# LAN8830_PINOUT.net
KiCad netlist of a schematic drawn in Altium Designer
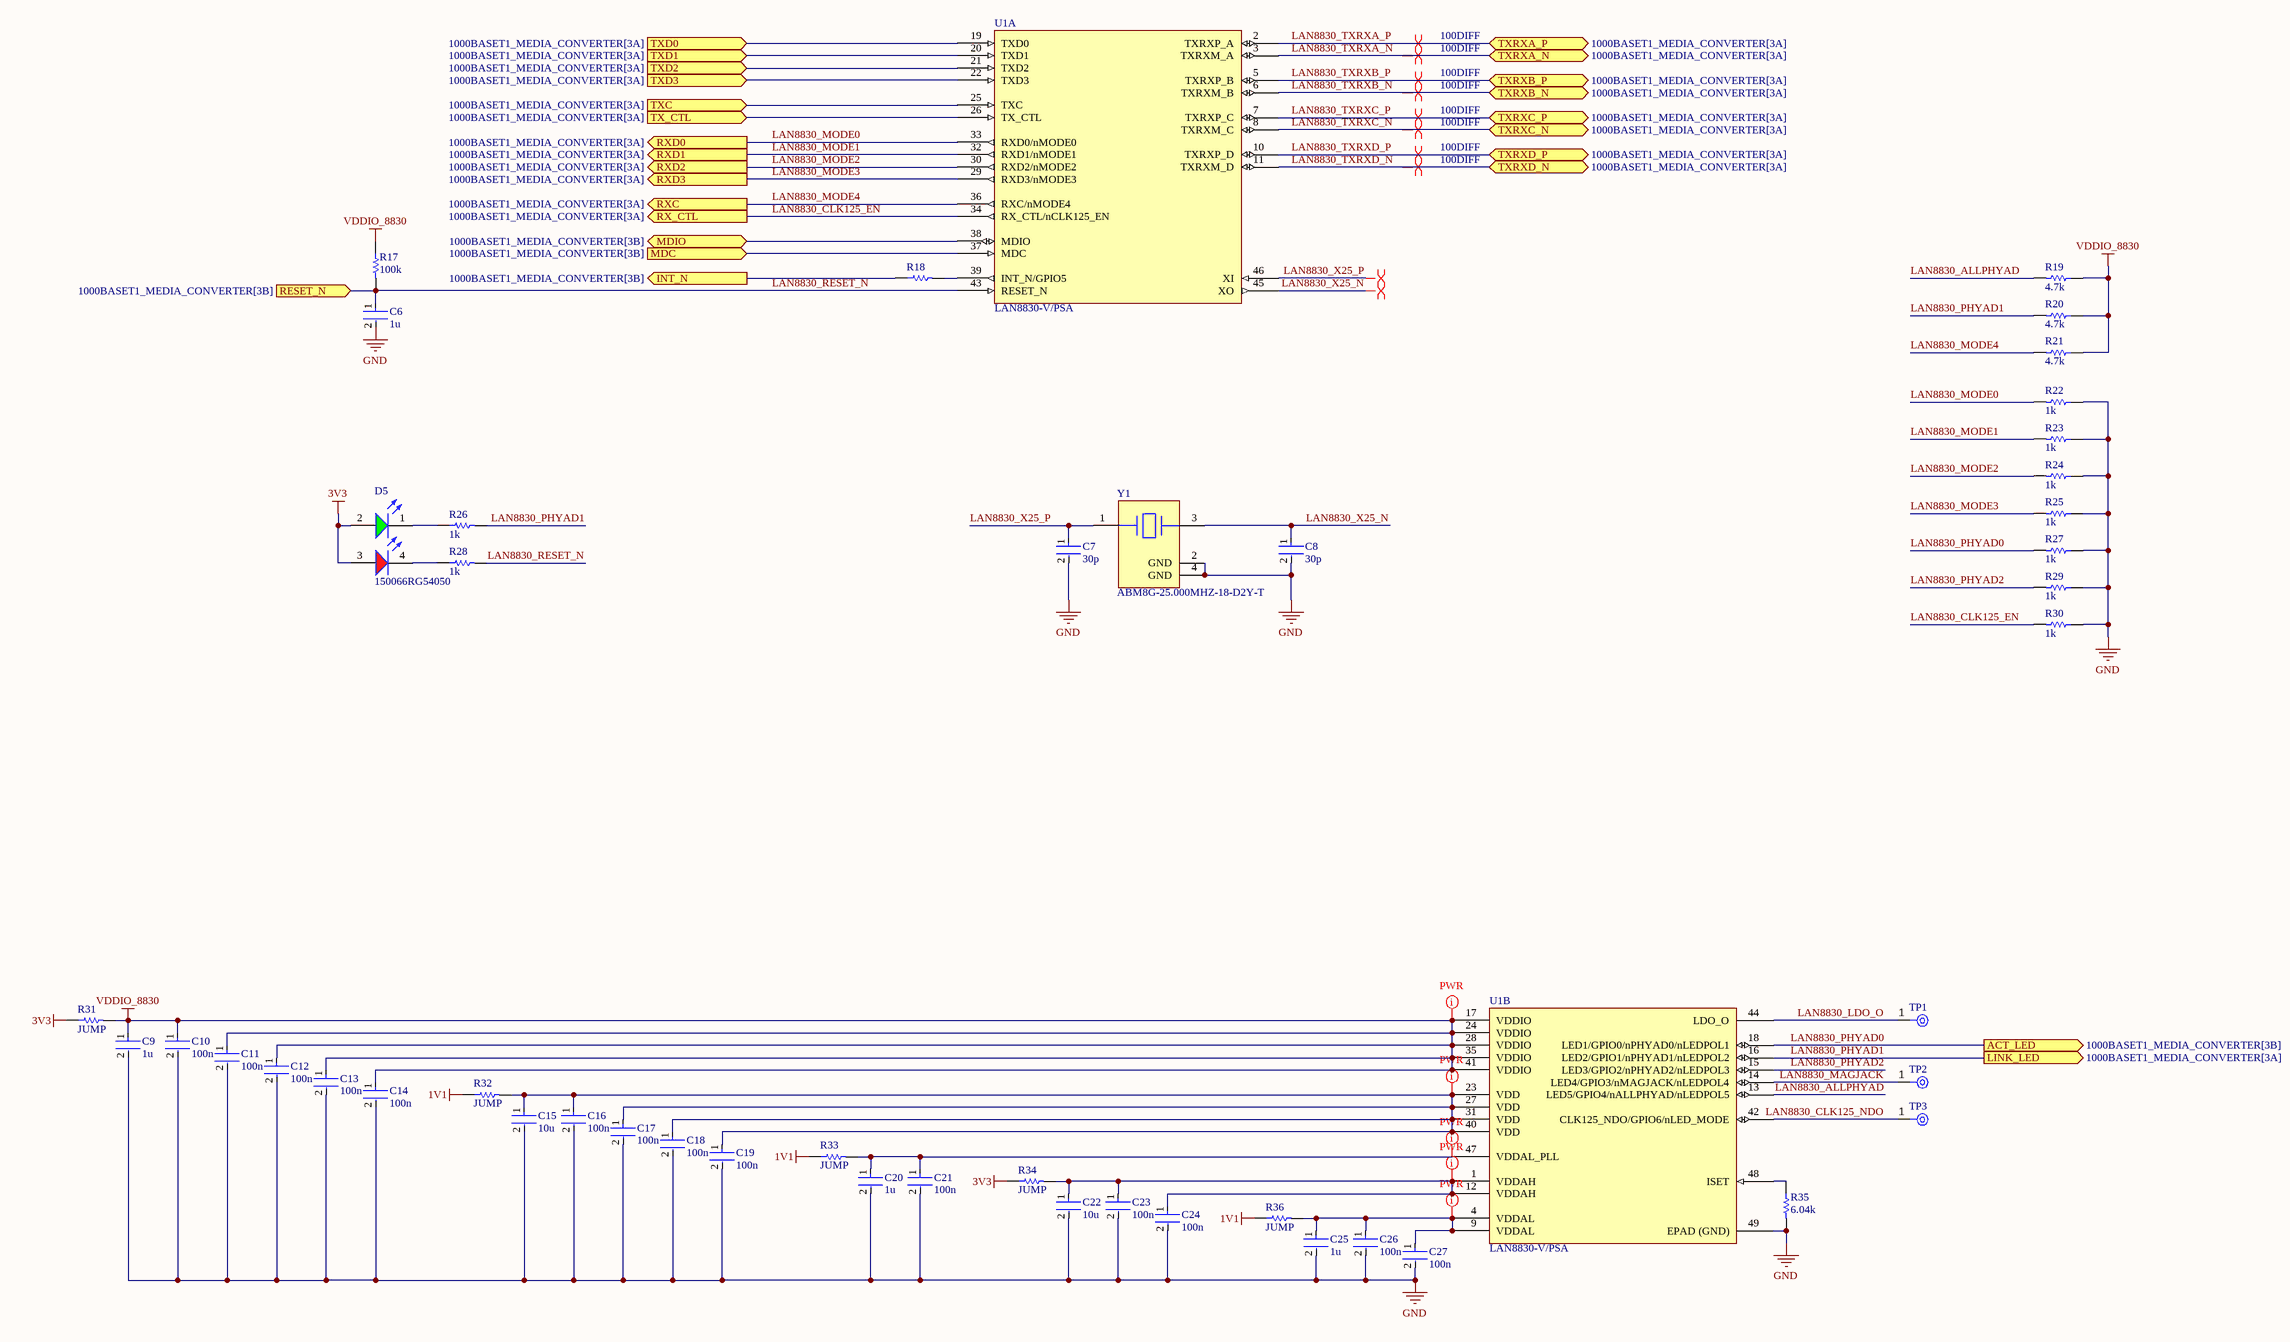
[diagram p0: LAN8830_PINOUT.SchDoc]

(export (version "E")
  (design (tool "Eeschema 10.0.6"))
  (components
    (comp (ref "C6")
      (value "1u")
      (footprint "FP-0402-L_1_0_0_05-W_0_5-IPC_A")
      (description "LARGE PADS, 0402 CAP, CHANGE COMMENT TO MATCH REAL P/N")
      (libsource (lib "Space Concordia") (part "b4654b650e69147ec39a6b967a45e02"))
    )
    (comp (ref "C7")
      (value "30p")
      (footprint "FP-0402-L_1_0_0_05-W_0_5-IPC_A")
      (description "LARGE PADS, 0402 CAP, CHANGE COMMENT TO MATCH REAL P/N")
      (libsource (lib "Space Concordia") (part "b4654b650e69147ec39a6b967a45e02"))
    )
    (comp (ref "C8")
      (value "30p")
      (footprint "FP-0402-L_1_0_0_05-W_0_5-IPC_A")
      (description "LARGE PADS, 0402 CAP, CHANGE COMMENT TO MATCH REAL P/N")
      (libsource (lib "Space Concordia") (part "b4654b650e69147ec39a6b967a45e02"))
    )
    (comp (ref "C9")
      (value "1u")
      (footprint "FP-0402-L_1_0_0_05-W_0_5-IPC_A")
      (description "LARGE PADS, 0402 CAP, CHANGE COMMENT TO MATCH REAL P/N")
      (libsource (lib "Space Concordia") (part "b4654b650e69147ec39a6b967a45e02"))
    )
    (comp (ref "C10")
      (value "100n")
      (footprint "FP-0402-L_1_0_0_05-W_0_5-IPC_A")
      (description "LARGE PADS, 0402 CAP, CHANGE COMMENT TO MATCH REAL P/N")
      (libsource (lib "Space Concordia") (part "b4654b650e69147ec39a6b967a45e02"))
    )
    (comp (ref "C11")
      (value "100n")
      (footprint "FP-0402-L_1_0_0_05-W_0_5-IPC_A")
      (description "LARGE PADS, 0402 CAP, CHANGE COMMENT TO MATCH REAL P/N")
      (libsource (lib "Space Concordia") (part "b4654b650e69147ec39a6b967a45e02"))
    )
    (comp (ref "C12")
      (value "100n")
      (footprint "FP-0402-L_1_0_0_05-W_0_5-IPC_A")
      (description "LARGE PADS, 0402 CAP, CHANGE COMMENT TO MATCH REAL P/N")
      (libsource (lib "Space Concordia") (part "b4654b650e69147ec39a6b967a45e02"))
    )
    (comp (ref "C13")
      (value "100n")
      (footprint "FP-0402-L_1_0_0_05-W_0_5-IPC_A")
      (description "LARGE PADS, 0402 CAP, CHANGE COMMENT TO MATCH REAL P/N")
      (libsource (lib "Space Concordia") (part "b4654b650e69147ec39a6b967a45e02"))
    )
    (comp (ref "C14")
      (value "100n")
      (footprint "FP-0402-L_1_0_0_05-W_0_5-IPC_A")
      (description "LARGE PADS, 0402 CAP, CHANGE COMMENT TO MATCH REAL P/N")
      (libsource (lib "Space Concordia") (part "b4654b650e69147ec39a6b967a45e02"))
    )
    (comp (ref "C15")
      (value "10u")
      (footprint "FP-0402-L_1_0_0_05-W_0_5-IPC_A")
      (description "LARGE PADS, 0402 CAP, CHANGE COMMENT TO MATCH REAL P/N")
      (libsource (lib "Space Concordia") (part "b4654b650e69147ec39a6b967a45e02"))
    )
    (comp (ref "C16")
      (value "100n")
      (footprint "FP-0402-L_1_0_0_05-W_0_5-IPC_A")
      (description "LARGE PADS, 0402 CAP, CHANGE COMMENT TO MATCH REAL P/N")
      (libsource (lib "Space Concordia") (part "b4654b650e69147ec39a6b967a45e02"))
    )
    (comp (ref "C17")
      (value "100n")
      (footprint "FP-0402-L_1_0_0_05-W_0_5-IPC_A")
      (description "LARGE PADS, 0402 CAP, CHANGE COMMENT TO MATCH REAL P/N")
      (libsource (lib "Space Concordia") (part "b4654b650e69147ec39a6b967a45e02"))
    )
    (comp (ref "C18")
      (value "100n")
      (footprint "FP-0402-L_1_0_0_05-W_0_5-IPC_A")
      (description "LARGE PADS, 0402 CAP, CHANGE COMMENT TO MATCH REAL P/N")
      (libsource (lib "Space Concordia") (part "b4654b650e69147ec39a6b967a45e02"))
    )
    (comp (ref "C19")
      (value "100n")
      (footprint "FP-0402-L_1_0_0_05-W_0_5-IPC_A")
      (description "LARGE PADS, 0402 CAP, CHANGE COMMENT TO MATCH REAL P/N")
      (libsource (lib "Space Concordia") (part "b4654b650e69147ec39a6b967a45e02"))
    )
    (comp (ref "C20")
      (value "1u")
      (footprint "FP-0402-L_1_0_0_05-W_0_5-IPC_A")
      (description "LARGE PADS, 0402 CAP, CHANGE COMMENT TO MATCH REAL P/N")
      (libsource (lib "Space Concordia") (part "b4654b650e69147ec39a6b967a45e02"))
    )
    (comp (ref "C21")
      (value "100n")
      (footprint "FP-0402-L_1_0_0_05-W_0_5-IPC_A")
      (description "LARGE PADS, 0402 CAP, CHANGE COMMENT TO MATCH REAL P/N")
      (libsource (lib "Space Concordia") (part "b4654b650e69147ec39a6b967a45e02"))
    )
    (comp (ref "C22")
      (value "10u")
      (footprint "FP-0402-L_1_0_0_05-W_0_5-IPC_A")
      (description "LARGE PADS, 0402 CAP, CHANGE COMMENT TO MATCH REAL P/N")
      (libsource (lib "Space Concordia") (part "b4654b650e69147ec39a6b967a45e02"))
    )
    (comp (ref "C23")
      (value "100n")
      (footprint "FP-0402-L_1_0_0_05-W_0_5-IPC_A")
      (description "LARGE PADS, 0402 CAP, CHANGE COMMENT TO MATCH REAL P/N")
      (libsource (lib "Space Concordia") (part "b4654b650e69147ec39a6b967a45e02"))
    )
    (comp (ref "C24")
      (value "100n")
      (footprint "FP-0402-L_1_0_0_05-W_0_5-IPC_A")
      (description "LARGE PADS, 0402 CAP, CHANGE COMMENT TO MATCH REAL P/N")
      (libsource (lib "Space Concordia") (part "b4654b650e69147ec39a6b967a45e02"))
    )
    (comp (ref "C25")
      (value "1u")
      (footprint "FP-0402-L_1_0_0_05-W_0_5-IPC_A")
      (description "LARGE PADS, 0402 CAP, CHANGE COMMENT TO MATCH REAL P/N")
      (libsource (lib "Space Concordia") (part "b4654b650e69147ec39a6b967a45e02"))
    )
    (comp (ref "C26")
      (value "100n")
      (footprint "FP-0402-L_1_0_0_05-W_0_5-IPC_A")
      (description "LARGE PADS, 0402 CAP, CHANGE COMMENT TO MATCH REAL P/N")
      (libsource (lib "Space Concordia") (part "b4654b650e69147ec39a6b967a45e02"))
    )
    (comp (ref "C27")
      (value "100n")
      (footprint "FP-0402-L_1_0_0_05-W_0_5-IPC_A")
      (description "LARGE PADS, 0402 CAP, CHANGE COMMENT TO MATCH REAL P/N")
      (libsource (lib "Space Concordia") (part "b4654b650e69147ec39a6b967a45e02"))
    )
    (comp (ref "D5")
      (value "150066RG54050")
      (footprint "WL-SBCD_0606")
      (description "Led, Red/Grn, 180Mcd/230Mcd, 624Nm/525Nm Rohs Compliant: Yes")
      (fields (field (name "SOURCE") "rgled.SchLib"))
      (libsource (lib "Space Concordia") (part "CMP-004-00034-2"))
    )
    (comp (ref "R17")
      (value "100k")
      (footprint "R0603B")
      (description "Resistor")
      (libsource (lib "Space Concordia") (part "Resistor"))
    )
    (comp (ref "R18")
      (value "0402 JUMPER")
      (footprint "RESC1005X40X25ML05T05")
      (description "READ THE NAME")
      (libsource (lib "Space Concordia") (part "CMP-009-00206-2"))
    )
    (comp (ref "R19")
      (value "4.7k")
      (footprint "R0603B")
      (description "Resistor")
      (libsource (lib "Space Concordia") (part "Resistor"))
    )
    (comp (ref "R20")
      (value "4.7k")
      (footprint "R0603B")
      (description "Resistor")
      (libsource (lib "Space Concordia") (part "Resistor"))
    )
    (comp (ref "R21")
      (value "4.7k")
      (footprint "R0603B")
      (description "Resistor")
      (libsource (lib "Space Concordia") (part "Resistor"))
    )
    (comp (ref "R22")
      (value "1k")
      (footprint "R0603B")
      (description "Resistor")
      (libsource (lib "Space Concordia") (part "Resistor"))
    )
    (comp (ref "R23")
      (value "1k")
      (footprint "R0603B")
      (description "Resistor")
      (libsource (lib "Space Concordia") (part "Resistor"))
    )
    (comp (ref "R24")
      (value "1k")
      (footprint "R0603B")
      (description "Resistor")
      (libsource (lib "Space Concordia") (part "Resistor"))
    )
    (comp (ref "R25")
      (value "1k")
      (footprint "R0603B")
      (description "Resistor")
      (libsource (lib "Space Concordia") (part "Resistor"))
    )
    (comp (ref "R26")
      (value "1k")
      (footprint "R0603B")
      (description "Resistor")
      (libsource (lib "Space Concordia") (part "Resistor"))
    )
    (comp (ref "R27")
      (value "1k")
      (footprint "R0603B")
      (description "Resistor")
      (libsource (lib "Space Concordia") (part "Resistor"))
    )
    (comp (ref "R28")
      (value "1k")
      (footprint "R0603B")
      (description "Resistor")
      (libsource (lib "Space Concordia") (part "Resistor"))
    )
    (comp (ref "R29")
      (value "1k")
      (footprint "R0603B")
      (description "Resistor")
      (libsource (lib "Space Concordia") (part "Resistor"))
    )
    (comp (ref "R30")
      (value "1k")
      (footprint "R0603B")
      (description "Resistor")
      (libsource (lib "Space Concordia") (part "Resistor"))
    )
    (comp (ref "R31")
      (value "JUMP")
      (footprint "R0603B")
      (description "Resistor")
      (libsource (lib "Space Concordia") (part "Resistor"))
    )
    (comp (ref "R32")
      (value "JUMP")
      (footprint "R0603B")
      (description "Resistor")
      (libsource (lib "Space Concordia") (part "Resistor"))
    )
    (comp (ref "R33")
      (value "JUMP")
      (footprint "R0603B")
      (description "Resistor")
      (libsource (lib "Space Concordia") (part "Resistor"))
    )
    (comp (ref "R34")
      (value "JUMP")
      (footprint "R0603B")
      (description "Resistor")
      (libsource (lib "Space Concordia") (part "Resistor"))
    )
    (comp (ref "R35")
      (value "6.04k")
      (footprint "R0603B")
      (description "Resistor")
      (libsource (lib "Space Concordia") (part "Resistor"))
    )
    (comp (ref "R36")
      (value "JUMP")
      (footprint "R0603B")
      (description "Resistor")
      (libsource (lib "Space Concordia") (part "Resistor"))
    )
    (comp (ref "TP1")
      (value "TPAD6R")
      (footprint "New footprint 1")
      (description "Test Point .6mm")
      (libsource (lib "Space Concordia") (part "TP"))
    )
    (comp (ref "TP2")
      (value "TPAD6R")
      (footprint "New footprint 1")
      (description "Test Point .6mm")
      (libsource (lib "Space Concordia") (part "TP"))
    )
    (comp (ref "TP3")
      (value "TPAD6R")
      (footprint "New footprint 1")
      (description "Test Point .6mm")
      (libsource (lib "Space Concordia") (part "TP"))
    )
    (comp (ref "U1")
      (value "LAN8830-V/PSA")
      (footprint "QFN50P700X700X100_HS-49N")
      (description "LAN8830 Series RGMII Interface Gigabit Ethernet Transceiver - VQFN-48")
      (libsource (lib "Space Concordia") (part "LAN8830-V_PSA"))
    )
    (comp (ref "Y1")
      (value "ABM8G-25.000MHZ-18-D2Y-T")
      (footprint "FP-ABM8G-MFG")
      (description "Crystal 25MHz ±20ppm (Tol) ±30ppm (Stability) 18pF FUND 60Ω 4-Pin SMD T/R")
      (fields (field (name "TOLERANCE") "20ppm"))
      (libsource (lib "Altium Content Vault") (part "48e526d86b7f2615d98721063c72f49"))
    )
  )
  (nets
    (net (code "1") (name "/INT_N") (class "Default")
      (node (ref "R18") (pin "1") (pinfunction "1_1") (pintype "passive"))
    )
    (net (code "2") (name "/LAN8830_ALLPHYAD") (class "Default")
      (node (ref "R19") (pin "2") (pinfunction "2_2") (pintype "passive"))
      (node (ref "U1") (pin "13") (pinfunction "LED5/GPIO4/nALLPHYAD/nLEDPOL5_13") (pintype "bidirectional"))
    )
    (net (code "3") (name "/LAN8830_CLK125_EN") (class "Default")
      (node (ref "R30") (pin "2") (pinfunction "2_2") (pintype "passive"))
      (node (ref "U1") (pin "34") (pinfunction "RX_CTL/nCLK125_EN_34") (pintype "output"))
    )
    (net (code "4") (name "/LAN8830_CLK125_NDO") (class "Default")
      (node (ref "TP3") (pin "1") (pinfunction "TP_1") (pintype "passive"))
      (node (ref "U1") (pin "42") (pinfunction "CLK125_NDO/GPIO6/nLED_MODE_42") (pintype "bidirectional"))
    )
    (net (code "5") (name "/LAN8830_LDO_O") (class "Default")
      (node (ref "TP1") (pin "1") (pinfunction "TP_1") (pintype "passive"))
      (node (ref "U1") (pin "44") (pinfunction "LDO_O_44") (pintype "power_in"))
    )
    (net (code "6") (name "/LAN8830_MAGJACK") (class "Default")
      (node (ref "TP2") (pin "1") (pinfunction "TP_1") (pintype "passive"))
      (node (ref "U1") (pin "14") (pinfunction "LED4/GPIO3/nMAGJACK/nLEDPOL4_14") (pintype "bidirectional"))
    )
    (net (code "7") (name "/LAN8830_MODE0") (class "Default")
      (node (ref "R22") (pin "2") (pinfunction "2_2") (pintype "passive"))
      (node (ref "U1") (pin "33") (pinfunction "RXD0/nMODE0_33") (pintype "output"))
    )
    (net (code "8") (name "/LAN8830_MODE1") (class "Default")
      (node (ref "R23") (pin "2") (pinfunction "2_2") (pintype "passive"))
      (node (ref "U1") (pin "32") (pinfunction "RXD1/nMODE1_32") (pintype "output"))
    )
    (net (code "9") (name "/LAN8830_MODE2") (class "Default")
      (node (ref "R24") (pin "2") (pinfunction "2_2") (pintype "passive"))
      (node (ref "U1") (pin "30") (pinfunction "RXD2/nMODE2_30") (pintype "output"))
    )
    (net (code "10") (name "/LAN8830_MODE3") (class "Default")
      (node (ref "R25") (pin "2") (pinfunction "2_2") (pintype "passive"))
      (node (ref "U1") (pin "29") (pinfunction "RXD3/nMODE3_29") (pintype "output"))
    )
    (net (code "11") (name "/LAN8830_MODE4") (class "Default")
      (node (ref "R21") (pin "2") (pinfunction "2_2") (pintype "passive"))
      (node (ref "U1") (pin "36") (pinfunction "RXC/nMODE4_36") (pintype "output"))
    )
    (net (code "12") (name "/LAN8830_PHYAD0") (class "Default")
      (node (ref "R27") (pin "2") (pinfunction "2_2") (pintype "passive"))
      (node (ref "U1") (pin "18") (pinfunction "LED1/GPIO0/nPHYAD0/nLEDPOL1_18") (pintype "bidirectional"))
    )
    (net (code "13") (name "/LAN8830_PHYAD1") (class "Default")
      (node (ref "R20") (pin "2") (pinfunction "2_2") (pintype "passive"))
      (node (ref "R26") (pin "2") (pinfunction "2_2") (pintype "passive"))
      (node (ref "U1") (pin "16") (pinfunction "LED2/GPIO1/nPHYAD1/nLEDPOL2_16") (pintype "bidirectional"))
    )
    (net (code "14") (name "/LAN8830_PHYAD2") (class "Default")
      (node (ref "R29") (pin "2") (pinfunction "2_2") (pintype "passive"))
      (node (ref "U1") (pin "15") (pinfunction "LED3/GPIO2/nPHYAD2/nLEDPOL3_15") (pintype "bidirectional"))
    )
    (net (code "15") (name "/LAN8830_RESET_N") (class "Default")
      (node (ref "C6") (pin "1") (pinfunction "1_1") (pintype "passive"))
      (node (ref "R17") (pin "2") (pinfunction "2_2") (pintype "passive"))
      (node (ref "R28") (pin "2") (pinfunction "2_2") (pintype "passive"))
      (node (ref "U1") (pin "43") (pinfunction "RESET_N_43") (pintype "input"))
    )
    (net (code "16") (name "/LAN8830_TXRXA_N") (class "Default")
      (node (ref "U1") (pin "3") (pinfunction "TXRXM_A_3") (pintype "bidirectional"))
    )
    (net (code "17") (name "/LAN8830_TXRXA_P") (class "Default")
      (node (ref "U1") (pin "2") (pinfunction "TXRXP_A_2") (pintype "bidirectional"))
    )
    (net (code "18") (name "/LAN8830_TXRXB_N") (class "Default")
      (node (ref "U1") (pin "6") (pinfunction "TXRXM_B_6") (pintype "bidirectional"))
    )
    (net (code "19") (name "/LAN8830_TXRXB_P") (class "Default")
      (node (ref "U1") (pin "5") (pinfunction "TXRXP_B_5") (pintype "bidirectional"))
    )
    (net (code "20") (name "/LAN8830_TXRXC_N") (class "Default")
      (node (ref "U1") (pin "8") (pinfunction "TXRXM_C_8") (pintype "bidirectional"))
    )
    (net (code "21") (name "/LAN8830_TXRXC_P") (class "Default")
      (node (ref "U1") (pin "7") (pinfunction "TXRXP_C_7") (pintype "bidirectional"))
    )
    (net (code "22") (name "/LAN8830_TXRXD_N") (class "Default")
      (node (ref "U1") (pin "11") (pinfunction "TXRXM_D_11") (pintype "bidirectional"))
    )
    (net (code "23") (name "/LAN8830_TXRXD_P") (class "Default")
      (node (ref "U1") (pin "10") (pinfunction "TXRXP_D_10") (pintype "bidirectional"))
    )
    (net (code "24") (name "/LAN8830_X25_N") (class "Default")
      (node (ref "C8") (pin "1") (pinfunction "1_1") (pintype "passive"))
      (node (ref "U1") (pin "45") (pinfunction "XO_45") (pintype "output"))
      (node (ref "Y1") (pin "3") (pinfunction "3_3") (pintype "passive"))
    )
    (net (code "25") (name "/LAN8830_X25_P") (class "Default")
      (node (ref "C7") (pin "1") (pinfunction "1_1") (pintype "passive"))
      (node (ref "U1") (pin "46") (pinfunction "XI_46") (pintype "input"))
      (node (ref "Y1") (pin "1") (pinfunction "1_1") (pintype "passive"))
    )
    (net (code "26") (name "/MDC") (class "Default")
      (node (ref "U1") (pin "37") (pinfunction "MDC_37") (pintype "input"))
    )
    (net (code "27") (name "/MDIO") (class "Default")
      (node (ref "U1") (pin "38") (pinfunction "MDIO_38") (pintype "bidirectional"))
    )
    (net (code "28") (name "/TXC") (class "Default")
      (node (ref "U1") (pin "25") (pinfunction "TXC_25") (pintype "input"))
    )
    (net (code "29") (name "/TXD0") (class "Default")
      (node (ref "U1") (pin "19") (pinfunction "TXD0_19") (pintype "input"))
    )
    (net (code "30") (name "/TXD1") (class "Default")
      (node (ref "U1") (pin "20") (pinfunction "TXD1_20") (pintype "input"))
    )
    (net (code "31") (name "/TXD2") (class "Default")
      (node (ref "U1") (pin "21") (pinfunction "TXD2_21") (pintype "input"))
    )
    (net (code "32") (name "/TXD3") (class "Default")
      (node (ref "U1") (pin "22") (pinfunction "TXD3_22") (pintype "input"))
    )
    (net (code "33") (name "/TX_CTL") (class "Default")
      (node (ref "U1") (pin "26") (pinfunction "TX_CTL_26") (pintype "input"))
    )
    (net (code "34") (name "1V1") (class "Default")
      (node (ref "R32") (pin "1") (pinfunction "1_1") (pintype "passive"))
      (node (ref "R33") (pin "1") (pinfunction "1_1") (pintype "passive"))
      (node (ref "R36") (pin "1") (pinfunction "1_1") (pintype "passive"))
    )
    (net (code "35") (name "3V3") (class "Default")
      (node (ref "D5") (pin "2") (pinfunction "A_2") (pintype "passive"))
      (node (ref "D5") (pin "3") (pinfunction "A_3") (pintype "passive"))
      (node (ref "R31") (pin "1") (pinfunction "1_1") (pintype "passive"))
      (node (ref "R34") (pin "1") (pinfunction "1_1") (pintype "passive"))
    )
    (net (code "36") (name "GND") (class "Default")
      (node (ref "C10") (pin "2") (pinfunction "2_2") (pintype "passive"))
      (node (ref "C11") (pin "2") (pinfunction "2_2") (pintype "passive"))
      (node (ref "C12") (pin "2") (pinfunction "2_2") (pintype "passive"))
      (node (ref "C13") (pin "2") (pinfunction "2_2") (pintype "passive"))
      (node (ref "C14") (pin "2") (pinfunction "2_2") (pintype "passive"))
      (node (ref "C15") (pin "2") (pinfunction "2_2") (pintype "passive"))
      (node (ref "C16") (pin "2") (pinfunction "2_2") (pintype "passive"))
      (node (ref "C17") (pin "2") (pinfunction "2_2") (pintype "passive"))
      (node (ref "C18") (pin "2") (pinfunction "2_2") (pintype "passive"))
      (node (ref "C19") (pin "2") (pinfunction "2_2") (pintype "passive"))
      (node (ref "C20") (pin "2") (pinfunction "2_2") (pintype "passive"))
      (node (ref "C21") (pin "2") (pinfunction "2_2") (pintype "passive"))
      (node (ref "C22") (pin "2") (pinfunction "2_2") (pintype "passive"))
      (node (ref "C23") (pin "2") (pinfunction "2_2") (pintype "passive"))
      (node (ref "C24") (pin "2") (pinfunction "2_2") (pintype "passive"))
      (node (ref "C25") (pin "2") (pinfunction "2_2") (pintype "passive"))
      (node (ref "C26") (pin "2") (pinfunction "2_2") (pintype "passive"))
      (node (ref "C27") (pin "2") (pinfunction "2_2") (pintype "passive"))
      (node (ref "C6") (pin "2") (pinfunction "2_2") (pintype "passive"))
      (node (ref "C7") (pin "2") (pinfunction "2_2") (pintype "passive"))
      (node (ref "C8") (pin "2") (pinfunction "2_2") (pintype "passive"))
      (node (ref "C9") (pin "2") (pinfunction "2_2") (pintype "passive"))
      (node (ref "R22") (pin "1") (pinfunction "1_1") (pintype "passive"))
      (node (ref "R23") (pin "1") (pinfunction "1_1") (pintype "passive"))
      (node (ref "R24") (pin "1") (pinfunction "1_1") (pintype "passive"))
      (node (ref "R25") (pin "1") (pinfunction "1_1") (pintype "passive"))
      (node (ref "R27") (pin "1") (pinfunction "1_1") (pintype "passive"))
      (node (ref "R29") (pin "1") (pinfunction "1_1") (pintype "passive"))
      (node (ref "R30") (pin "1") (pinfunction "1_1") (pintype "passive"))
      (node (ref "R35") (pin "2") (pinfunction "2_2") (pintype "passive"))
      (node (ref "U1") (pin "49") (pinfunction "EPAD_(GND)_49") (pintype "power_in"))
      (node (ref "Y1") (pin "2") (pinfunction "GND_2") (pintype "power_in"))
      (node (ref "Y1") (pin "4") (pinfunction "GND_4") (pintype "power_in"))
    )
    (net (code "37") (name "Net-(C15-Pad1)") (class "Default")
      (node (ref "C15") (pin "1") (pinfunction "1_1") (pintype "passive"))
      (node (ref "C16") (pin "1") (pinfunction "1_1") (pintype "passive"))
      (node (ref "C17") (pin "1") (pinfunction "1_1") (pintype "passive"))
      (node (ref "C18") (pin "1") (pinfunction "1_1") (pintype "passive"))
      (node (ref "C19") (pin "1") (pinfunction "1_1") (pintype "passive"))
      (node (ref "R32") (pin "2") (pinfunction "2_2") (pintype "passive"))
      (node (ref "U1") (pin "23") (pinfunction "VDD_23") (pintype "power_in"))
      (node (ref "U1") (pin "27") (pinfunction "VDD_27") (pintype "power_in"))
      (node (ref "U1") (pin "31") (pinfunction "VDD_31") (pintype "power_in"))
      (node (ref "U1") (pin "40") (pinfunction "VDD_40") (pintype "power_in"))
    )
    (net (code "38") (name "Net-(C22-Pad1)") (class "Default")
      (node (ref "C22") (pin "1") (pinfunction "1_1") (pintype "passive"))
      (node (ref "C23") (pin "1") (pinfunction "1_1") (pintype "passive"))
      (node (ref "C24") (pin "1") (pinfunction "1_1") (pintype "passive"))
      (node (ref "R34") (pin "2") (pinfunction "2_2") (pintype "passive"))
      (node (ref "U1") (pin "1") (pinfunction "VDDAH_1") (pintype "power_in"))
      (node (ref "U1") (pin "12") (pinfunction "VDDAH_12") (pintype "power_in"))
    )
    (net (code "39") (name "Net-(C25-Pad1)") (class "Default")
      (node (ref "C25") (pin "1") (pinfunction "1_1") (pintype "passive"))
      (node (ref "C26") (pin "1") (pinfunction "1_1") (pintype "passive"))
      (node (ref "C27") (pin "1") (pinfunction "1_1") (pintype "passive"))
      (node (ref "R36") (pin "2") (pinfunction "2_2") (pintype "passive"))
      (node (ref "U1") (pin "4") (pinfunction "VDDAL_4") (pintype "power_in"))
      (node (ref "U1") (pin "9") (pinfunction "VDDAL_9") (pintype "power_in"))
    )
    (net (code "40") (name "Net-(D5-K-Pad1)") (class "Default")
      (node (ref "D5") (pin "1") (pinfunction "K_1") (pintype "passive"))
      (node (ref "R26") (pin "1") (pinfunction "1_1") (pintype "passive"))
    )
    (net (code "41") (name "Net-(D5-K-Pad4)") (class "Default")
      (node (ref "D5") (pin "4") (pinfunction "K_4") (pintype "passive"))
      (node (ref "R28") (pin "1") (pinfunction "1_1") (pintype "passive"))
    )
    (net (code "42") (name "Net-(U1A-INT_N{slash}GPIO5)") (class "Default")
      (node (ref "R18") (pin "2") (pinfunction "2_2") (pintype "passive"))
      (node (ref "U1") (pin "39") (pinfunction "INT_N/GPIO5_39") (pintype "output"))
    )
    (net (code "43") (name "Net-(U1B-ISET)") (class "Default")
      (node (ref "R35") (pin "1") (pinfunction "1_1") (pintype "passive"))
      (node (ref "U1") (pin "48") (pinfunction "ISET_48") (pintype "input"))
    )
    (net (code "44") (name "Net-(U1B-VDDAL_PLL)") (class "Default")
      (node (ref "C20") (pin "1") (pinfunction "1_1") (pintype "passive"))
      (node (ref "C21") (pin "1") (pinfunction "1_1") (pintype "passive"))
      (node (ref "R33") (pin "2") (pinfunction "2_2") (pintype "passive"))
      (node (ref "U1") (pin "47") (pinfunction "VDDAL_PLL_47") (pintype "power_in"))
    )
    (net (code "45") (name "VDDIO_8830") (class "Default")
      (node (ref "C10") (pin "1") (pinfunction "1_1") (pintype "passive"))
      (node (ref "C11") (pin "1") (pinfunction "1_1") (pintype "passive"))
      (node (ref "C12") (pin "1") (pinfunction "1_1") (pintype "passive"))
      (node (ref "C13") (pin "1") (pinfunction "1_1") (pintype "passive"))
      (node (ref "C14") (pin "1") (pinfunction "1_1") (pintype "passive"))
      (node (ref "C9") (pin "1") (pinfunction "1_1") (pintype "passive"))
      (node (ref "R17") (pin "1") (pinfunction "1_1") (pintype "passive"))
      (node (ref "R19") (pin "1") (pinfunction "1_1") (pintype "passive"))
      (node (ref "R20") (pin "1") (pinfunction "1_1") (pintype "passive"))
      (node (ref "R21") (pin "1") (pinfunction "1_1") (pintype "passive"))
      (node (ref "R31") (pin "2") (pinfunction "2_2") (pintype "passive"))
      (node (ref "U1") (pin "17") (pinfunction "VDDIO_17") (pintype "power_in"))
      (node (ref "U1") (pin "24") (pinfunction "VDDIO_24") (pintype "power_in"))
      (node (ref "U1") (pin "28") (pinfunction "VDDIO_28") (pintype "power_in"))
      (node (ref "U1") (pin "35") (pinfunction "VDDIO_35") (pintype "power_in"))
      (node (ref "U1") (pin "41") (pinfunction "VDDIO_41") (pintype "power_in"))
    )
  )
)
